# Net520.net
KiCad netlist of a schematic drawn in Altium Designer
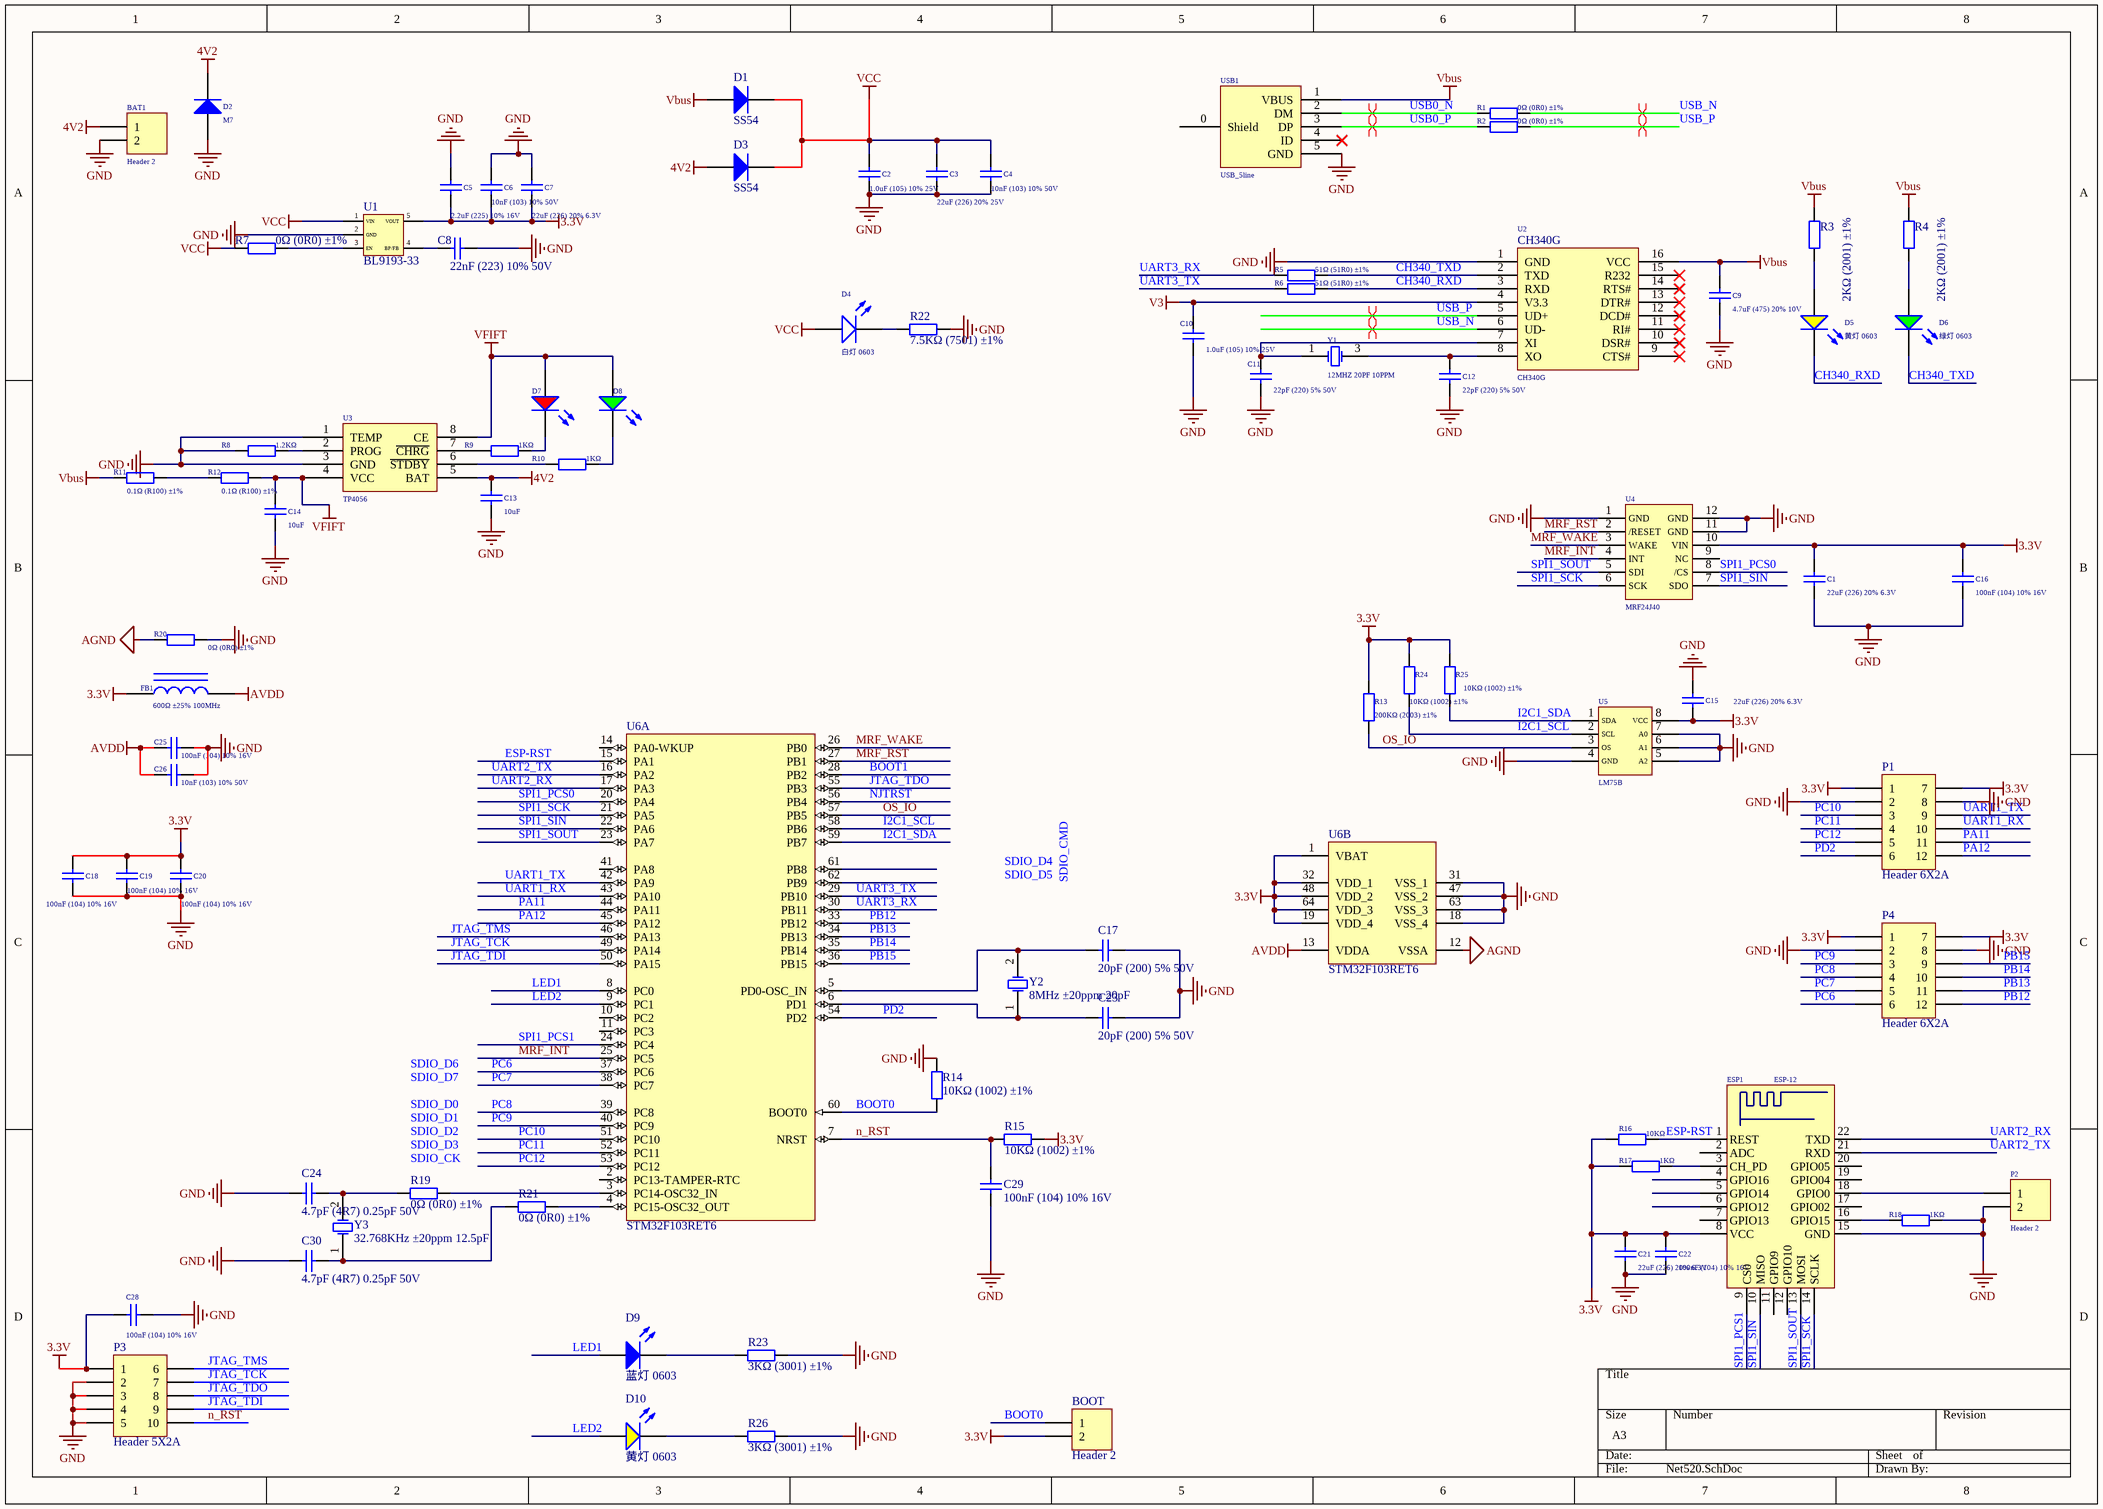
[diagram p0: Net520.SchDoc]

(export (version "E")
  (design (tool "Eeschema 10.0.6"))
  (components
    (comp (ref "BAT1")
      (value "Header 2")
      (footprint "HDR1X2")
      (description "Header, 2-Pin")
      (fields (field (name "PUBLISHER") "Altium Limited"))
      (libsource (lib "Sparks") (part "Header 2"))
    )
    (comp (ref "BOOT")
      (value "Header 2")
      (footprint "HDR1X2")
      (description "Header, 2-Pin")
      (fields (field (name "PUBLISHER") "Altium Limited"))
      (libsource (lib "Sparks") (part "Header 2"))
    )
    (comp (ref "C1")
      (value "22uF (226) 20% 6.3V")
      (footprint "0603_C")
      (description "贴片电容")
      (libsource (lib "Miscellaneous Devices LC") (part "0603 22uF (226) 20% 6.3V"))
    )
    (comp (ref "C2")
      (value "1.0uF (105) 10% 25V")
      (footprint "0402_C")
      (description "贴片电容")
      (libsource (lib "Miscellaneous Devices LC") (part "0402 1.0uF (105) 10% 25V"))
    )
    (comp (ref "C3")
      (value "22uF (226) 20% 25V")
      (footprint "0805_C")
      (description "贴片电容")
      (libsource (lib "Miscellaneous Devices LC") (part "0805 22uF (226) 20% 25V"))
    )
    (comp (ref "C4")
      (value "10nF (103) 10% 50V")
      (footprint "0402_C")
      (description "贴片电容")
      (libsource (lib "Miscellaneous Devices LC") (part "0402 10nF (103) 10% 50V"))
    )
    (comp (ref "C5")
      (value "2.2uF (225) 10% 16V")
      (footprint "0603_C")
      (description "贴片电容")
      (libsource (lib "Miscellaneous Devices LC") (part "0603 2.2uF (225) 10% 16V"))
    )
    (comp (ref "C6")
      (value "10nF (103) 10% 50V")
      (footprint "0402_C")
      (description "贴片电容")
      (libsource (lib "Miscellaneous Devices LC") (part "0402 10nF (103) 10% 50V"))
    )
    (comp (ref "C7")
      (value "22uF (226) 20% 6.3V")
      (footprint "0603_C")
      (description "贴片电容")
      (libsource (lib "Miscellaneous Devices LC") (part "0603 22uF (226) 20% 6.3V"))
    )
    (comp (ref "C8")
      (value "22nF (223) 10% 50V")
      (footprint "0402_C")
      (description "贴片电容")
      (libsource (lib "Miscellaneous Devices LC") (part "0402 22nF (223) 10% 50V"))
    )
    (comp (ref "C9")
      (value "4.7uF (475) 20% 10V")
      (footprint "0402_C")
      (description "贴片电容")
      (libsource (lib "Miscellaneous Devices LC") (part "0402 4.7uF (475) 20% 10V"))
    )
    (comp (ref "C10")
      (value "1.0uF (105) 10% 25V")
      (footprint "0402_C")
      (description "贴片电容")
      (libsource (lib "Miscellaneous Devices LC") (part "0402 1.0uF (105) 10% 25V"))
    )
    (comp (ref "C11")
      (value "22pF (220) 5% 50V")
      (footprint "0402_C")
      (description "贴片电容")
      (libsource (lib "Miscellaneous Devices LC") (part "0402 22pF (220) 5% 50V"))
    )
    (comp (ref "C12")
      (value "22pF (220) 5% 50V")
      (footprint "0402_C")
      (description "贴片电容")
      (libsource (lib "Miscellaneous Devices LC") (part "0402 22pF (220) 5% 50V"))
    )
    (comp (ref "C13")
      (value "10uF")
      (footprint "0402_C")
      (description "贴片电容")
      (libsource (lib "Cap") (part "0402 10uF (106) 20% 6.3V"))
    )
    (comp (ref "C14")
      (value "10uF")
      (footprint "0402_C")
      (description "贴片电容")
      (libsource (lib "Cap") (part "0402 10uF (106) 20% 6.3V"))
    )
    (comp (ref "C15")
      (value "22uF (226) 20% 6.3V")
      (footprint "0603_C")
      (description "贴片电容")
      (libsource (lib "Miscellaneous Devices LC") (part "0603 22uF (226) 20% 6.3V"))
    )
    (comp (ref "C16")
      (value "100nF (104) 10% 16V")
      (footprint "0402_C")
      (description "贴片电容")
      (libsource (lib "Miscellaneous Devices LC") (part "0402 100nF (104) 10% 16V"))
    )
    (comp (ref "C17")
      (value "20pF (200) 5% 50V")
      (footprint "0402_C")
      (description "贴片电容")
      (libsource (lib "Miscellaneous Devices LC") (part "0402 20pF (200) 5% 50V"))
    )
    (comp (ref "C18")
      (value "100nF (104) 10% 16V")
      (footprint "0402_C")
      (description "贴片电容")
      (libsource (lib "Miscellaneous Devices LC") (part "0402 100nF (104) 10% 16V"))
    )
    (comp (ref "C19")
      (value "100nF (104) 10% 16V")
      (footprint "0402_C")
      (description "贴片电容")
      (libsource (lib "Miscellaneous Devices LC") (part "0402 100nF (104) 10% 16V"))
    )
    (comp (ref "C20")
      (value "100nF (104) 10% 16V")
      (footprint "0402_C")
      (description "贴片电容")
      (libsource (lib "Miscellaneous Devices LC") (part "0402 100nF (104) 10% 16V"))
    )
    (comp (ref "C21")
      (value "22uF (226) 20% 6.3V")
      (footprint "0603_C")
      (description "贴片电容")
      (libsource (lib "Miscellaneous Devices LC") (part "0603 22uF (226) 20% 6.3V"))
    )
    (comp (ref "C22")
      (value "100nF (104) 10% 16V")
      (footprint "0402_C")
      (description "贴片电容")
      (libsource (lib "Miscellaneous Devices LC") (part "0402 100nF (104) 10% 16V"))
    )
    (comp (ref "C23")
      (value "20pF (200) 5% 50V")
      (footprint "0402_C")
      (description "贴片电容")
      (libsource (lib "Miscellaneous Devices LC") (part "0402 20pF (200) 5% 50V"))
    )
    (comp (ref "C24")
      (value "4.7pF (4R7) 0.25pF 50V")
      (footprint "0402_C")
      (description "贴片电容")
      (libsource (lib "Miscellaneous Devices LC") (part "0402 4.7pF (4R7) 0.25pF 50V"))
    )
    (comp (ref "C25")
      (value "100nF (104) 10% 16V")
      (footprint "0402_C")
      (description "贴片电容")
      (libsource (lib "Miscellaneous Devices LC") (part "0402 100nF (104) 10% 16V"))
    )
    (comp (ref "C26")
      (value "10nF (103) 10% 50V")
      (footprint "0402_C")
      (description "贴片电容")
      (libsource (lib "Miscellaneous Devices LC") (part "0402 10nF (103) 10% 50V"))
    )
    (comp (ref "C28")
      (value "100nF (104) 10% 16V")
      (footprint "0402_C")
      (description "贴片电容")
      (libsource (lib "Miscellaneous Devices LC") (part "0402 100nF (104) 10% 16V"))
    )
    (comp (ref "C29")
      (value "100nF (104) 10% 16V")
      (footprint "0402_C")
      (description "贴片电容")
      (libsource (lib "Miscellaneous Devices LC") (part "0402 100nF (104) 10% 16V"))
    )
    (comp (ref "C30")
      (value "4.7pF (4R7) 0.25pF 50V")
      (footprint "0402_C")
      (description "贴片电容")
      (libsource (lib "Miscellaneous Devices LC") (part "0402 4.7pF (4R7) 0.25pF 50V"))
    )
    (comp (ref "D1")
      (value "SS54")
      (footprint "SMA(DO-214AC)_S1")
      (description "二极管")
      (libsource (lib "Miscellaneous Devices LC") (part "SMA(DO-214AC) SS54"))
    )
    (comp (ref "D2")
      (value "M7")
      (footprint "SMA(DO-214AC)_S1")
      (description "二极管")
      (libsource (lib "Miscellaneous Devices LC") (part "SMA(DO-214AC) M7"))
    )
    (comp (ref "D3")
      (value "SS54")
      (footprint "SMA(DO-214AC)_S1")
      (description "二极管")
      (libsource (lib "Miscellaneous Devices LC") (part "SMA(DO-214AC) SS54"))
    )
    (comp (ref "D4")
      (value "白灯 0603")
      (footprint "0603_LED_S1")
      (description "发光二极管")
      (libsource (lib "Miscellaneous Devices LC") (part "0603 白灯"))
    )
    (comp (ref "D5")
      (value "黄灯 0603")
      (footprint "0603_LED_S1")
      (description "发光二极管")
      (libsource (lib "Miscellaneous Devices LC") (part "0603 黄灯"))
    )
    (comp (ref "D6")
      (value "绿灯 0603")
      (footprint "0603_LED_S1")
      (description "发光二极管")
      (libsource (lib "Miscellaneous Devices LC") (part "0603 绿灯"))
    )
    (comp (ref "D7")
      (value "红灯 0603")
      (footprint "0603_LED_S1")
      (description "发光二极管")
      (libsource (lib "LED") (part "0603 红灯"))
    )
    (comp (ref "D8")
      (value "绿灯 0603")
      (footprint "0603_LED_S1")
      (description "发光二极管")
      (libsource (lib "LED") (part "0603 绿灯"))
    )
    (comp (ref "D9")
      (value "蓝灯 0603")
      (footprint "0603_LED_S1")
      (description "发光二极管")
      (libsource (lib "Miscellaneous Devices LC") (part "0603 蓝灯"))
    )
    (comp (ref "D10")
      (value "黄灯 0603")
      (footprint "0603_LED_S1")
      (description "发光二极管")
      (libsource (lib "Miscellaneous Devices LC") (part "0603 黄灯"))
    )
    (comp (ref "ESP1") (value "ESP-12") (footprint "ESP-12") (libsource (lib "2号库") (part "ESP-12")))
    (comp (ref "FB1")
      (value "600Ω ±25% 100MHz")
      (footprint "0805_L")
      (description "贴片磁珠")
      (libsource (lib "Miscellaneous Devices LC") (part "0805 600Ω 25% 100MHz"))
    )
    (comp (ref "P1")
      (value "Header 6X2A")
      (footprint "SMT-HEADER 6*2")
      (description "Header, 6-Pin, Dual row")
      (fields (field (name "PUBLISHER") "Altium Limited"))
      (libsource (lib "Miscellaneous Connectors") (part "Header 6X2A"))
    )
    (comp (ref "P2")
      (value "Header 2")
      (footprint "HDR1X2")
      (description "Header, 2-Pin")
      (fields (field (name "PUBLISHER") "Altium Limited"))
      (libsource (lib "Sparks") (part "Header 2"))
    )
    (comp (ref "P3")
      (value "Header 5X2A")
      (footprint "SMT HEADER 5*2")
      (description "Header, 5-Pin, Dual row")
      (fields (field (name "PUBLISHER") "Altium Limited"))
      (libsource (lib "Miscellaneous Connectors") (part "Header 5X2A"))
    )
    (comp (ref "P4")
      (value "Header 6X2A")
      (footprint "SMT-HEADER 6*2")
      (description "Header, 6-Pin, Dual row")
      (fields (field (name "PUBLISHER") "Altium Limited"))
      (libsource (lib "Miscellaneous Connectors") (part "Header 6X2A"))
    )
    (comp (ref "R1")
      (value "0Ω (0R0) ±1%")
      (footprint "0402_R")
      (description "贴片电阻")
      (libsource (lib "Miscellaneous Devices LC") (part "0402 0Ω (0R0) 1%"))
    )
    (comp (ref "R2")
      (value "0Ω (0R0) ±1%")
      (footprint "0402_R")
      (description "贴片电阻")
      (libsource (lib "Miscellaneous Devices LC") (part "0402 0Ω (0R0) 1%"))
    )
    (comp (ref "R3")
      (value "2KΩ (2001) ±1%")
      (footprint "0402_R")
      (description "贴片电阻")
      (libsource (lib "Miscellaneous Devices LC") (part "0402 2KΩ (2001) 1%"))
    )
    (comp (ref "R4")
      (value "2KΩ (2001) ±1%")
      (footprint "0402_R")
      (description "贴片电阻")
      (libsource (lib "") (part "0402 2KΩ (2001) 1%_1"))
    )
    (comp (ref "R5")
      (value "51Ω (51R0) ±1%")
      (footprint "0402_R")
      (description "贴片电阻")
      (libsource (lib "Miscellaneous Devices LC") (part "0402 51Ω (51R0) 1%"))
    )
    (comp (ref "R6")
      (value "51Ω (51R0) ±1%")
      (footprint "0402_R")
      (description "贴片电阻")
      (libsource (lib "Miscellaneous Devices LC") (part "0402 51Ω (51R0) 1%"))
    )
    (comp (ref "R7")
      (value "0Ω (0R0) ±1%")
      (footprint "0402_R")
      (description "贴片电阻")
      (libsource (lib "Miscellaneous Devices LC") (part "0402 0Ω (0R0) 1%"))
    )
    (comp (ref "R8")
      (value "1.2KΩ")
      (footprint "0402_R")
      (description "贴片电阻")
      (libsource (lib "RES") (part "0402 1.2KΩ (1201) 1%"))
    )
    (comp (ref "R9")
      (value "1KΩ")
      (footprint "0402_R")
      (description "贴片电阻")
      (libsource (lib "RES") (part "0402 1KΩ (1001) 1%"))
    )
    (comp (ref "R10")
      (value "1KΩ")
      (footprint "0402_R")
      (description "贴片电阻")
      (libsource (lib "RES") (part "0402 1KΩ (1001) 1%"))
    )
    (comp (ref "R11")
      (value "0.1Ω (R100) ±1%")
      (footprint "1206_R")
      (description "贴片电阻")
      (libsource (lib "Miscellaneous Devices LC") (part "1206 0.1Ω (R100) 1%"))
    )
    (comp (ref "R12")
      (value "0.1Ω (R100) ±1%")
      (footprint "1206_R")
      (description "贴片电阻")
      (libsource (lib "Miscellaneous Devices LC") (part "1206 0.1Ω (R100) 1%"))
    )
    (comp (ref "R13")
      (value "200KΩ (2003) ±1%")
      (footprint "0402_R")
      (description "贴片电阻")
      (libsource (lib "Miscellaneous Devices LC") (part "0402 200KΩ (2003) 1%"))
    )
    (comp (ref "R14")
      (value "10KΩ (1002) ±1%")
      (footprint "0402_R")
      (description "贴片电阻")
      (libsource (lib "Miscellaneous Devices LC") (part "0402 10KΩ (1002) 1%"))
    )
    (comp (ref "R15")
      (value "10KΩ (1002) ±1%")
      (footprint "0402_R")
      (description "贴片电阻")
      (libsource (lib "") (part "0402 10KΩ (1002) 1%_1"))
    )
    (comp (ref "R16")
      (value "10KΩ")
      (footprint "0603_R")
      (description "贴片电阻")
      (libsource (lib "RES") (part "0603 10KΩ (1002) 1%"))
    )
    (comp (ref "R17")
      (value "1KΩ")
      (footprint "0603_R")
      (description "贴片电阻")
      (libsource (lib "RES") (part "0603 1KΩ (1001) 1%"))
    )
    (comp (ref "R18")
      (value "1KΩ")
      (footprint "0603_R")
      (description "贴片电阻")
      (libsource (lib "RES") (part "0603 1KΩ (1001) 1%"))
    )
    (comp (ref "R19")
      (value "0Ω (0R0) ±1%")
      (footprint "0402_R")
      (description "贴片电阻")
      (libsource (lib "Miscellaneous Devices LC") (part "0402 0Ω (0R0) 1%"))
    )
    (comp (ref "R20")
      (value "0Ω (0R0) ±1%")
      (footprint "0402_R")
      (description "贴片电阻")
      (libsource (lib "Miscellaneous Devices LC") (part "0402 0Ω (0R0) 1%"))
    )
    (comp (ref "R21")
      (value "0Ω (0R0) ±1%")
      (footprint "0402_R")
      (description "贴片电阻")
      (libsource (lib "Miscellaneous Devices LC") (part "0402 0Ω (0R0) 1%"))
    )
    (comp (ref "R22")
      (value "7.5KΩ (7501) ±1%")
      (footprint "0402_R")
      (description "贴片电阻")
      (libsource (lib "Miscellaneous Devices LC") (part "0402 7.5KΩ (7501) 1%"))
    )
    (comp (ref "R23")
      (value "3KΩ (3001) ±1%")
      (footprint "0603_R")
      (description "贴片电阻")
      (libsource (lib "Miscellaneous Devices LC") (part "0603 3KΩ (3001) 1%"))
    )
    (comp (ref "R24")
      (value "10KΩ (1002) ±1%")
      (footprint "0402_R")
      (description "贴片电阻")
      (libsource (lib "Miscellaneous Devices LC") (part "0402 10KΩ (1002) 1%"))
    )
    (comp (ref "R25")
      (value "10KΩ (1002) ±1%")
      (footprint "0402_R")
      (description "贴片电阻")
      (libsource (lib "Miscellaneous Devices LC") (part "0402 10KΩ (1002) 1%"))
    )
    (comp (ref "R26")
      (value "3KΩ (3001) ±1%")
      (footprint "0603_R")
      (description "贴片电阻")
      (libsource (lib "Miscellaneous Devices LC") (part "0603 3KΩ (3001) 1%"))
    )
    (comp (ref "U1")
      (value "BL9193-33")
      (footprint "LC-SOT-23-5")
      (libsource (lib "jlcUser") (part "BL9193-33"))
    )
    (comp (ref "U2")
      (value "CH340G")
      (footprint "SOIC-16_150mil")
      (description "USB")
      (libsource (lib "Miscellaneous Devices LC") (part "CH340G_[C14267]"))
    )
    (comp (ref "U3")
      (value "TP4056")
      (footprint "SOP-8_EP_150mil")
      (description "电池电源管理")
      (libsource (lib "IC") (part "TP4056_[C16581]"))
    )
    (comp (ref "U4") (value "MRF24J40") (footprint "MRF24J40") (libsource (lib "2号库") (part "MRF24J40")))
    (comp (ref "U5")
      (value "LM75B")
      (footprint "LC-SOIC-8_150mil")
      (libsource (lib "jlcUser") (part "LM75B"))
    )
    (comp (ref "U6")
      (value "STM32F103RET6")
      (footprint "LQFP-64_10x10x05P")
      (description "ARM")
      (libsource (lib "Miscellaneous Devices LC") (part "STM32F103RET6"))
    )
    (comp (ref "USB1")
      (value "USB_5line")
      (footprint "USB-MICRO-5P-2F")
      (libsource (lib "2号库") (part "USB_5line"))
    )
    (comp (ref "Y1")
      (value "12MHZ 20PF 10PPM")
      (footprint "SMD-3225_4P")
      (description "贴片晶振")
      (libsource (lib "Miscellaneous Devices LC") (part "SMD-3225_4P  12MHZ 20PF 10PPM"))
    )
    (comp (ref "Y2")
      (value "8MHz ±20ppm 20pF")
      (footprint "SMD-5032_2P")
      (description "贴片晶振")
      (libsource (lib "Miscellaneous Devices LC") (part "SMD-5032_2P 8MHz 20ppm 20pF"))
    )
    (comp (ref "Y3")
      (value "32.768KHz ±20ppm 12.5pF")
      (footprint "SMD-3215_2P FC - 135")
      (description "贴片晶振")
      (libsource (lib "Miscellaneous Devices LC") (part "SMD-3215_2P 32.768KHz 20ppm 12.5pF"))
    )
  )
  (nets
    (net (code "1") (name "/BOOT0") (class "Default")
      (node (ref "BOOT") (pin "1") (pinfunction "1_1") (pintype "passive"))
      (node (ref "R14") (pin "1") (pinfunction "1_1") (pintype "passive"))
      (node (ref "U6") (pin "60") (pinfunction "BOOT0_60") (pintype "input"))
    )
    (net (code "2") (name "/BOOT1") (class "Default")
      (node (ref "U6") (pin "28") (pinfunction "PB2_28") (pintype "bidirectional"))
    )
    (net (code "3") (name "/CH340_RXD") (class "Default")
      (node (ref "D5") (pin "K") (pinfunction "K_K") (pintype "passive"))
      (node (ref "R6") (pin "2") (pinfunction "2_2") (pintype "passive"))
      (node (ref "U2") (pin "3") (pinfunction "RXD_3") (pintype "passive"))
    )
    (net (code "4") (name "/CH340_TXD") (class "Default")
      (node (ref "D6") (pin "K") (pinfunction "K_K") (pintype "passive"))
      (node (ref "R5") (pin "2") (pinfunction "2_2") (pintype "passive"))
      (node (ref "U2") (pin "2") (pinfunction "TXD_2") (pintype "passive"))
    )
    (net (code "5") (name "/ESP-RST") (class "Default")
      (node (ref "ESP1") (pin "1") (pinfunction "REST_1") (pintype "passive"))
      (node (ref "R16") (pin "2") (pinfunction "2_2") (pintype "passive"))
      (node (ref "U6") (pin "15") (pinfunction "PA1_15") (pintype "bidirectional"))
    )
    (net (code "6") (name "/I2C1_SCL") (class "Default")
      (node (ref "R24") (pin "1") (pinfunction "1_1") (pintype "passive"))
      (node (ref "U5") (pin "2") (pinfunction "SCL_2") (pintype "passive"))
      (node (ref "U6") (pin "58") (pinfunction "PB6_58") (pintype "bidirectional"))
    )
    (net (code "7") (name "/I2C1_SDA") (class "Default")
      (node (ref "R25") (pin "1") (pinfunction "1_1") (pintype "passive"))
      (node (ref "U5") (pin "1") (pinfunction "SDA_1") (pintype "passive"))
      (node (ref "U6") (pin "59") (pinfunction "PB7_59") (pintype "bidirectional"))
    )
    (net (code "8") (name "/JTAG_TCK") (class "Default")
      (node (ref "P3") (pin "7") (pinfunction "7_7") (pintype "passive"))
      (node (ref "U6") (pin "49") (pinfunction "PA14_49") (pintype "bidirectional"))
    )
    (net (code "9") (name "/JTAG_TDI") (class "Default")
      (node (ref "P3") (pin "9") (pinfunction "9_9") (pintype "passive"))
      (node (ref "U6") (pin "50") (pinfunction "PA15_50") (pintype "bidirectional"))
    )
    (net (code "10") (name "/JTAG_TDO") (class "Default")
      (node (ref "P3") (pin "8") (pinfunction "8_8") (pintype "passive"))
      (node (ref "U6") (pin "55") (pinfunction "PB3_55") (pintype "bidirectional"))
    )
    (net (code "11") (name "/JTAG_TMS") (class "Default")
      (node (ref "P3") (pin "6") (pinfunction "6_6") (pintype "passive"))
      (node (ref "U6") (pin "46") (pinfunction "PA13_46") (pintype "bidirectional"))
    )
    (net (code "12") (name "/LED1") (class "Default")
      (node (ref "D9") (pin "A") (pinfunction "A_A") (pintype "passive"))
      (node (ref "U6") (pin "8") (pinfunction "PC0_8") (pintype "bidirectional"))
    )
    (net (code "13") (name "/LED2") (class "Default")
      (node (ref "D10") (pin "A") (pinfunction "A_A") (pintype "passive"))
      (node (ref "U6") (pin "9") (pinfunction "PC1_9") (pintype "bidirectional"))
    )
    (net (code "14") (name "/MRF_INT") (class "Default")
      (node (ref "U4") (pin "4") (pinfunction "INT_4") (pintype "passive"))
      (node (ref "U6") (pin "25") (pinfunction "PC5_25") (pintype "bidirectional"))
    )
    (net (code "15") (name "/MRF_RST") (class "Default")
      (node (ref "U4") (pin "2") (pinfunction "/RESET_2") (pintype "passive"))
      (node (ref "U6") (pin "27") (pinfunction "PB1_27") (pintype "bidirectional"))
    )
    (net (code "16") (name "/MRF_WAKE") (class "Default")
      (node (ref "U4") (pin "3") (pinfunction "WAKE_3") (pintype "passive"))
      (node (ref "U6") (pin "26") (pinfunction "PB0_26") (pintype "bidirectional"))
    )
    (net (code "17") (name "/NJTRST") (class "Default")
      (node (ref "U6") (pin "56") (pinfunction "PB4_56") (pintype "bidirectional"))
    )
    (net (code "18") (name "/OS_IO") (class "Default")
      (node (ref "R13") (pin "1") (pinfunction "1_1") (pintype "passive"))
      (node (ref "U5") (pin "3") (pinfunction "OS_3") (pintype "passive"))
      (node (ref "U6") (pin "57") (pinfunction "PB5_57") (pintype "bidirectional"))
    )
    (net (code "19") (name "/PA11") (class "Default")
      (node (ref "P1") (pin "11") (pinfunction "11_11") (pintype "passive"))
      (node (ref "U6") (pin "44") (pinfunction "PA11_44") (pintype "bidirectional"))
    )
    (net (code "20") (name "/PA12") (class "Default")
      (node (ref "P1") (pin "12") (pinfunction "12_12") (pintype "passive"))
      (node (ref "U6") (pin "45") (pinfunction "PA12_45") (pintype "bidirectional"))
    )
    (net (code "21") (name "/PB12") (class "Default")
      (node (ref "P4") (pin "12") (pinfunction "12_12") (pintype "passive"))
      (node (ref "U6") (pin "33") (pinfunction "PB12_33") (pintype "bidirectional"))
    )
    (net (code "22") (name "/PB13") (class "Default")
      (node (ref "P4") (pin "11") (pinfunction "11_11") (pintype "passive"))
      (node (ref "U6") (pin "34") (pinfunction "PB13_34") (pintype "bidirectional"))
    )
    (net (code "23") (name "/PB14") (class "Default")
      (node (ref "P4") (pin "10") (pinfunction "10_10") (pintype "passive"))
      (node (ref "U6") (pin "35") (pinfunction "PB14_35") (pintype "bidirectional"))
    )
    (net (code "24") (name "/PB15") (class "Default")
      (node (ref "P4") (pin "9") (pinfunction "9_9") (pintype "passive"))
      (node (ref "U6") (pin "36") (pinfunction "PB15_36") (pintype "bidirectional"))
    )
    (net (code "25") (name "/PC6") (class "Default")
      (node (ref "P4") (pin "6") (pinfunction "6_6") (pintype "passive"))
      (node (ref "U6") (pin "37") (pinfunction "PC6_37") (pintype "bidirectional"))
    )
    (net (code "26") (name "/PC7") (class "Default")
      (node (ref "P4") (pin "5") (pinfunction "5_5") (pintype "passive"))
      (node (ref "U6") (pin "38") (pinfunction "PC7_38") (pintype "bidirectional"))
    )
    (net (code "27") (name "/PC8") (class "Default")
      (node (ref "P4") (pin "4") (pinfunction "4_4") (pintype "passive"))
      (node (ref "U6") (pin "39") (pinfunction "PC8_39") (pintype "bidirectional"))
    )
    (net (code "28") (name "/PC9") (class "Default")
      (node (ref "P4") (pin "3") (pinfunction "3_3") (pintype "passive"))
      (node (ref "U6") (pin "40") (pinfunction "PC9_40") (pintype "bidirectional"))
    )
    (net (code "29") (name "/PC10") (class "Default")
      (node (ref "P1") (pin "3") (pinfunction "3_3") (pintype "passive"))
      (node (ref "U6") (pin "51") (pinfunction "PC10_51") (pintype "bidirectional"))
    )
    (net (code "30") (name "/PC11") (class "Default")
      (node (ref "P1") (pin "4") (pinfunction "4_4") (pintype "passive"))
      (node (ref "U6") (pin "52") (pinfunction "PC11_52") (pintype "bidirectional"))
    )
    (net (code "31") (name "/PC12") (class "Default")
      (node (ref "P1") (pin "5") (pinfunction "5_5") (pintype "passive"))
      (node (ref "U6") (pin "53") (pinfunction "PC12_53") (pintype "bidirectional"))
    )
    (net (code "32") (name "/PD2") (class "Default")
      (node (ref "P1") (pin "6") (pinfunction "6_6") (pintype "passive"))
      (node (ref "U6") (pin "54") (pinfunction "PD2_54") (pintype "bidirectional"))
    )
    (net (code "43") (name "/SPI1_PCS0") (class "Default")
      (node (ref "U4") (pin "8") (pinfunction "/CS_8") (pintype "passive"))
      (node (ref "U6") (pin "20") (pinfunction "PA4_20") (pintype "bidirectional"))
    )
    (net (code "44") (name "/SPI1_PCS1") (class "Default")
      (node (ref "ESP1") (pin "9") (pinfunction "CS0_9") (pintype "passive"))
      (node (ref "U6") (pin "24") (pinfunction "PC4_24") (pintype "bidirectional"))
    )
    (net (code "45") (name "/SPI1_SCK") (class "Default")
      (node (ref "ESP1") (pin "14") (pinfunction "SCLK_14") (pintype "passive"))
      (node (ref "U4") (pin "6") (pinfunction "SCK_6") (pintype "passive"))
      (node (ref "U6") (pin "21") (pinfunction "PA5_21") (pintype "bidirectional"))
    )
    (net (code "46") (name "/SPI1_SIN") (class "Default")
      (node (ref "ESP1") (pin "10") (pinfunction "MISO_10") (pintype "passive"))
      (node (ref "U4") (pin "7") (pinfunction "SDO_7") (pintype "passive"))
      (node (ref "U6") (pin "22") (pinfunction "PA6_22") (pintype "bidirectional"))
    )
    (net (code "47") (name "/SPI1_SOUT") (class "Default")
      (node (ref "ESP1") (pin "13") (pinfunction "MOSI_13") (pintype "passive"))
      (node (ref "U4") (pin "5") (pinfunction "SDI_5") (pintype "passive"))
      (node (ref "U6") (pin "23") (pinfunction "PA7_23") (pintype "bidirectional"))
    )
    (net (code "48") (name "/UART1_RX") (class "Default")
      (node (ref "P1") (pin "10") (pinfunction "10_10") (pintype "passive"))
      (node (ref "U6") (pin "43") (pinfunction "PA10_43") (pintype "bidirectional"))
    )
    (net (code "49") (name "/UART1_TX") (class "Default")
      (node (ref "P1") (pin "9") (pinfunction "9_9") (pintype "passive"))
      (node (ref "U6") (pin "42") (pinfunction "PA9_42") (pintype "bidirectional"))
    )
    (net (code "50") (name "/UART2_RX") (class "Default")
      (node (ref "ESP1") (pin "22") (pinfunction "TXD_22") (pintype "passive"))
      (node (ref "U6") (pin "17") (pinfunction "PA3_17") (pintype "bidirectional"))
    )
    (net (code "51") (name "/UART2_TX") (class "Default")
      (node (ref "ESP1") (pin "21") (pinfunction "RXD_21") (pintype "passive"))
      (node (ref "U6") (pin "16") (pinfunction "PA2_16") (pintype "bidirectional"))
    )
    (net (code "52") (name "/UART3_RX") (class "Default")
      (node (ref "R5") (pin "1") (pinfunction "1_1") (pintype "passive"))
      (node (ref "U6") (pin "30") (pinfunction "PB11_30") (pintype "bidirectional"))
    )
    (net (code "53") (name "/UART3_TX") (class "Default")
      (node (ref "R6") (pin "1") (pinfunction "1_1") (pintype "passive"))
      (node (ref "U6") (pin "29") (pinfunction "PB10_29") (pintype "bidirectional"))
    )
    (net (code "54") (name "/USB0_N") (class "Default")
      (node (ref "R1") (pin "1") (pinfunction "1_1") (pintype "passive"))
      (node (ref "USB1") (pin "2") (pinfunction "DM_2") (pintype "passive"))
    )
    (net (code "55") (name "/USB0_P") (class "Default")
      (node (ref "R2") (pin "1") (pinfunction "1_1") (pintype "passive"))
      (node (ref "USB1") (pin "3") (pinfunction "DP_3") (pintype "passive"))
    )
    (net (code "56") (name "/USB_N") (class "Default")
      (node (ref "R1") (pin "2") (pinfunction "2_2") (pintype "passive"))
      (node (ref "U2") (pin "6") (pinfunction "UD-_6") (pintype "passive"))
    )
    (net (code "57") (name "/USB_P") (class "Default")
      (node (ref "R2") (pin "2") (pinfunction "2_2") (pintype "passive"))
      (node (ref "U2") (pin "5") (pinfunction "UD+_5") (pintype "passive"))
    )
    (net (code "58") (name "/n_RST") (class "Default")
      (node (ref "C29") (pin "2") (pinfunction "2_2") (pintype "passive"))
      (node (ref "P3") (pin "10") (pinfunction "10_10") (pintype "passive"))
      (node (ref "R15") (pin "2") (pinfunction "2_2") (pintype "passive"))
      (node (ref "U6") (pin "7") (pinfunction "NRST_7") (pintype "bidirectional"))
    )
    (net (code "59") (name "3.3V") (class "Default")
      (node (ref "BOOT") (pin "2") (pinfunction "2_2") (pintype "passive"))
      (node (ref "C1") (pin "2") (pinfunction "2_2") (pintype "passive"))
      (node (ref "C15") (pin "1") (pinfunction "1_1") (pintype "passive"))
      (node (ref "C16") (pin "2") (pinfunction "2_2") (pintype "passive"))
      (node (ref "C18") (pin "2") (pinfunction "2_2") (pintype "passive"))
      (node (ref "C19") (pin "2") (pinfunction "2_2") (pintype "passive"))
      (node (ref "C20") (pin "2") (pinfunction "2_2") (pintype "passive"))
      (node (ref "C21") (pin "2") (pinfunction "2_2") (pintype "passive"))
      (node (ref "C22") (pin "2") (pinfunction "2_2") (pintype "passive"))
      (node (ref "C28") (pin "1") (pinfunction "1_1") (pintype "passive"))
      (node (ref "C5") (pin "1") (pinfunction "1_1") (pintype "passive"))
      (node (ref "C6") (pin "1") (pinfunction "1_1") (pintype "passive"))
      (node (ref "C7") (pin "1") (pinfunction "1_1") (pintype "passive"))
      (node (ref "ESP1") (pin "8") (pinfunction "VCC_8") (pintype "passive"))
      (node (ref "FB1") (pin "1") (pinfunction "1_1") (pintype "passive"))
      (node (ref "P1") (pin "1") (pinfunction "1_1") (pintype "passive"))
      (node (ref "P1") (pin "7") (pinfunction "7_7") (pintype "passive"))
      (node (ref "P3") (pin "1") (pinfunction "1_1") (pintype "passive"))
      (node (ref "P4") (pin "1") (pinfunction "1_1") (pintype "passive"))
      (node (ref "P4") (pin "7") (pinfunction "7_7") (pintype "passive"))
      (node (ref "R13") (pin "2") (pinfunction "2_2") (pintype "passive"))
      (node (ref "R15") (pin "1") (pinfunction "1_1") (pintype "passive"))
      (node (ref "R16") (pin "1") (pinfunction "1_1") (pintype "passive"))
      (node (ref "R17") (pin "1") (pinfunction "1_1") (pintype "passive"))
      (node (ref "R24") (pin "2") (pinfunction "2_2") (pintype "passive"))
      (node (ref "R25") (pin "2") (pinfunction "2_2") (pintype "passive"))
      (node (ref "U1") (pin "5") (pinfunction "VOUT_5") (pintype "passive"))
      (node (ref "U4") (pin "10") (pinfunction "VIN_10") (pintype "passive"))
      (node (ref "U5") (pin "8") (pinfunction "VCC_8") (pintype "passive"))
      (node (ref "U6") (pin "1") (pinfunction "VBAT_1") (pintype "power_in"))
      (node (ref "U6") (pin "19") (pinfunction "VDD_4_19") (pintype "power_in"))
      (node (ref "U6") (pin "32") (pinfunction "VDD_1_32") (pintype "power_in"))
      (node (ref "U6") (pin "48") (pinfunction "VDD_2_48") (pintype "power_in"))
      (node (ref "U6") (pin "64") (pinfunction "VDD_3_64") (pintype "power_in"))
    )
    (net (code "60") (name "4V2") (class "Default")
      (node (ref "BAT1") (pin "1") (pinfunction "1_1") (pintype "passive"))
      (node (ref "C13") (pin "2") (pinfunction "2_2") (pintype "passive"))
      (node (ref "D2") (pin "2") (pinfunction "K_2") (pintype "passive"))
      (node (ref "D3") (pin "1") (pinfunction "A_1") (pintype "passive"))
      (node (ref "U3") (pin "5") (pinfunction "BAT_5") (pintype "passive"))
    )
    (net (code "61") (name "AGND") (class "Default")
      (node (ref "R20") (pin "1") (pinfunction "1_1") (pintype "passive"))
      (node (ref "U6") (pin "12") (pinfunction "VSSA_12") (pintype "power_in"))
    )
    (net (code "62") (name "AVDD") (class "Default")
      (node (ref "C25") (pin "1") (pinfunction "1_1") (pintype "passive"))
      (node (ref "C26") (pin "1") (pinfunction "1_1") (pintype "passive"))
      (node (ref "FB1") (pin "2") (pinfunction "2_2") (pintype "passive"))
      (node (ref "U6") (pin "13") (pinfunction "VDDA_13") (pintype "power_in"))
    )
    (net (code "63") (name "GND") (class "Default")
      (node (ref "BAT1") (pin "2") (pinfunction "2_2") (pintype "passive"))
      (node (ref "C1") (pin "1") (pinfunction "1_1") (pintype "passive"))
      (node (ref "C10") (pin "1") (pinfunction "1_1") (pintype "passive"))
      (node (ref "C11") (pin "1") (pinfunction "1_1") (pintype "passive"))
      (node (ref "C12") (pin "1") (pinfunction "1_1") (pintype "passive"))
      (node (ref "C13") (pin "1") (pinfunction "1_1") (pintype "passive"))
      (node (ref "C14") (pin "1") (pinfunction "1_1") (pintype "passive"))
      (node (ref "C15") (pin "2") (pinfunction "2_2") (pintype "passive"))
      (node (ref "C16") (pin "1") (pinfunction "1_1") (pintype "passive"))
      (node (ref "C17") (pin "1") (pinfunction "1_1") (pintype "passive"))
      (node (ref "C18") (pin "1") (pinfunction "1_1") (pintype "passive"))
      (node (ref "C19") (pin "1") (pinfunction "1_1") (pintype "passive"))
      (node (ref "C2") (pin "1") (pinfunction "1_1") (pintype "passive"))
      (node (ref "C20") (pin "1") (pinfunction "1_1") (pintype "passive"))
      (node (ref "C21") (pin "1") (pinfunction "1_1") (pintype "passive"))
      (node (ref "C22") (pin "1") (pinfunction "1_1") (pintype "passive"))
      (node (ref "C23") (pin "1") (pinfunction "1_1") (pintype "passive"))
      (node (ref "C24") (pin "1") (pinfunction "1_1") (pintype "passive"))
      (node (ref "C25") (pin "2") (pinfunction "2_2") (pintype "passive"))
      (node (ref "C26") (pin "2") (pinfunction "2_2") (pintype "passive"))
      (node (ref "C28") (pin "2") (pinfunction "2_2") (pintype "passive"))
      (node (ref "C29") (pin "1") (pinfunction "1_1") (pintype "passive"))
      (node (ref "C3") (pin "1") (pinfunction "1_1") (pintype "passive"))
      (node (ref "C30") (pin "1") (pinfunction "1_1") (pintype "passive"))
      (node (ref "C4") (pin "1") (pinfunction "1_1") (pintype "passive"))
      (node (ref "C5") (pin "2") (pinfunction "2_2") (pintype "passive"))
      (node (ref "C6") (pin "2") (pinfunction "2_2") (pintype "passive"))
      (node (ref "C7") (pin "2") (pinfunction "2_2") (pintype "passive"))
      (node (ref "C8") (pin "2") (pinfunction "2_2") (pintype "passive"))
      (node (ref "C9") (pin "1") (pinfunction "1_1") (pintype "passive"))
      (node (ref "D2") (pin "1") (pinfunction "A_1") (pintype "passive"))
      (node (ref "ESP1") (pin "15") (pinfunction "GND_15") (pintype "passive"))
      (node (ref "P1") (pin "2") (pinfunction "2_2") (pintype "passive"))
      (node (ref "P1") (pin "8") (pinfunction "8_8") (pintype "passive"))
      (node (ref "P2") (pin "2") (pinfunction "2_2") (pintype "passive"))
      (node (ref "P3") (pin "2") (pinfunction "2_2") (pintype "passive"))
      (node (ref "P3") (pin "3") (pinfunction "3_3") (pintype "passive"))
      (node (ref "P3") (pin "4") (pinfunction "4_4") (pintype "passive"))
      (node (ref "P3") (pin "5") (pinfunction "5_5") (pintype "passive"))
      (node (ref "P4") (pin "2") (pinfunction "2_2") (pintype "passive"))
      (node (ref "P4") (pin "8") (pinfunction "8_8") (pintype "passive"))
      (node (ref "R14") (pin "2") (pinfunction "2_2") (pintype "passive"))
      (node (ref "R18") (pin "2") (pinfunction "2_2") (pintype "passive"))
      (node (ref "R20") (pin "2") (pinfunction "2_2") (pintype "passive"))
      (node (ref "R22") (pin "2") (pinfunction "2_2") (pintype "passive"))
      (node (ref "R23") (pin "2") (pinfunction "2_2") (pintype "passive"))
      (node (ref "R26") (pin "2") (pinfunction "2_2") (pintype "passive"))
      (node (ref "R8") (pin "1") (pinfunction "1_1") (pintype "passive"))
      (node (ref "U1") (pin "2") (pinfunction "GND_2") (pintype "passive"))
      (node (ref "U2") (pin "1") (pinfunction "GND_1") (pintype "passive"))
      (node (ref "U3") (pin "1") (pinfunction "TEMP_1") (pintype "passive"))
      (node (ref "U3") (pin "3") (pinfunction "GND_3") (pintype "passive"))
      (node (ref "U4") (pin "1") (pinfunction "GND_1") (pintype "passive"))
      (node (ref "U4") (pin "11") (pinfunction "GND_11") (pintype "passive"))
      (node (ref "U4") (pin "12") (pinfunction "GND_12") (pintype "passive"))
      (node (ref "U5") (pin "4") (pinfunction "GND_4") (pintype "passive"))
      (node (ref "U5") (pin "5") (pinfunction "A2_5") (pintype "passive"))
      (node (ref "U5") (pin "6") (pinfunction "A1_6") (pintype "passive"))
      (node (ref "U5") (pin "7") (pinfunction "A0_7") (pintype "passive"))
      (node (ref "U6") (pin "18") (pinfunction "VSS_4_18") (pintype "power_in"))
      (node (ref "U6") (pin "31") (pinfunction "VSS_1_31") (pintype "power_in"))
      (node (ref "U6") (pin "47") (pinfunction "VSS_2_47") (pintype "power_in"))
      (node (ref "U6") (pin "63") (pinfunction "VSS_3_63") (pintype "power_in"))
      (node (ref "USB1") (pin "5") (pinfunction "GND_5") (pintype "passive"))
    )
    (net (code "64") (name "Net-(D4-PadK)") (class "Default")
      (node (ref "D4") (pin "K") (pinfunction "K_K") (pintype "passive"))
      (node (ref "R22") (pin "1") (pinfunction "1_1") (pintype "passive"))
    )
    (net (code "65") (name "Net-(D5-PadA)") (class "Default")
      (node (ref "D5") (pin "A") (pinfunction "A_A") (pintype "passive"))
      (node (ref "R3") (pin "1") (pinfunction "1_1") (pintype "passive"))
    )
    (net (code "66") (name "Net-(D6-PadA)") (class "Default")
      (node (ref "D6") (pin "A") (pinfunction "A_A") (pintype "passive"))
      (node (ref "R4") (pin "2") (pinfunction "2_2") (pintype "passive"))
    )
    (net (code "67") (name "Net-(D7-PadK)") (class "Default")
      (node (ref "D7") (pin "K") (pinfunction "K_K") (pintype "passive"))
      (node (ref "R9") (pin "2") (pinfunction "2_2") (pintype "passive"))
    )
    (net (code "68") (name "Net-(D8-PadK)") (class "Default")
      (node (ref "D8") (pin "K") (pinfunction "K_K") (pintype "passive"))
      (node (ref "R10") (pin "2") (pinfunction "2_2") (pintype "passive"))
    )
    (net (code "69") (name "Net-(D9-PadK)") (class "Default")
      (node (ref "D9") (pin "K") (pinfunction "K_K") (pintype "passive"))
      (node (ref "R23") (pin "1") (pinfunction "1_1") (pintype "passive"))
    )
    (net (code "70") (name "Net-(D10-PadK)") (class "Default")
      (node (ref "D10") (pin "K") (pinfunction "K_K") (pintype "passive"))
      (node (ref "R26") (pin "1") (pinfunction "1_1") (pintype "passive"))
    )
    (net (code "71") (name "Net-(ESP1-CH_PD)") (class "Default")
      (node (ref "ESP1") (pin "3") (pinfunction "CH_PD_3") (pintype "passive"))
      (node (ref "R17") (pin "2") (pinfunction "2_2") (pintype "passive"))
    )
    (net (code "72") (name "Net-(ESP1-GPIO0)") (class "Default")
      (node (ref "ESP1") (pin "18") (pinfunction "GPIO0_18") (pintype "passive"))
      (node (ref "P2") (pin "1") (pinfunction "1_1") (pintype "passive"))
    )
    (net (code "73") (name "Net-(ESP1-GPIO15)") (class "Default")
      (node (ref "ESP1") (pin "16") (pinfunction "GPIO15_16") (pintype "passive"))
      (node (ref "R18") (pin "1") (pinfunction "1_1") (pintype "passive"))
    )
    (net (code "74") (name "Net-(R11-Pad2)") (class "Default")
      (node (ref "R11") (pin "2") (pinfunction "2_2") (pintype "passive"))
      (node (ref "R12") (pin "1") (pinfunction "1_1") (pintype "passive"))
    )
    (net (code "75") (name "Net-(U1-BP{slash}FB)") (class "Default")
      (node (ref "C8") (pin "1") (pinfunction "1_1") (pintype "passive"))
      (node (ref "U1") (pin "4") (pinfunction "BP/FB_4") (pintype "passive"))
    )
    (net (code "76") (name "Net-(U1-EN)") (class "Default")
      (node (ref "R7") (pin "2") (pinfunction "2_2") (pintype "passive"))
      (node (ref "U1") (pin "3") (pinfunction "EN_3") (pintype "passive"))
    )
    (net (code "77") (name "Net-(U2-XI)") (class "Default")
      (node (ref "C11") (pin "2") (pinfunction "2_2") (pintype "passive"))
      (node (ref "U2") (pin "7") (pinfunction "XI_7") (pintype "passive"))
      (node (ref "Y1") (pin "1") (pinfunction "OSC1_1") (pintype "passive"))
    )
    (net (code "78") (name "Net-(U2-XO)") (class "Default")
      (node (ref "C12") (pin "2") (pinfunction "2_2") (pintype "passive"))
      (node (ref "U2") (pin "8") (pinfunction "XO_8") (pintype "passive"))
      (node (ref "Y1") (pin "3") (pinfunction "OSC2_3") (pintype "passive"))
    )
    (net (code "79") (name "Net-(U3-PROG)") (class "Default")
      (node (ref "R8") (pin "2") (pinfunction "2_2") (pintype "passive"))
      (node (ref "U3") (pin "2") (pinfunction "PROG_2") (pintype "passive"))
    )
    (net (code "80") (name "Net-(U3-~{CHRG})") (class "Default")
      (node (ref "R9") (pin "1") (pinfunction "1_1") (pintype "passive"))
      (node (ref "U3") (pin "7") (pinfunction "~{CHRG}_7") (pintype "passive"))
    )
    (net (code "81") (name "Net-(U3-~{STDBY})") (class "Default")
      (node (ref "R10") (pin "1") (pinfunction "1_1") (pintype "passive"))
      (node (ref "U3") (pin "6") (pinfunction "~{STDBY}_6") (pintype "passive"))
    )
    (net (code "82") (name "Net-(U6A-PC14-OSC32_IN)") (class "Default")
      (node (ref "R19") (pin "2") (pinfunction "2_2") (pintype "passive"))
      (node (ref "U6") (pin "3") (pinfunction "PC14-OSC32_IN_3") (pintype "bidirectional"))
    )
    (net (code "83") (name "Net-(U6A-PC15-OSC32_OUT)") (class "Default")
      (node (ref "R21") (pin "2") (pinfunction "2_2") (pintype "passive"))
      (node (ref "U6") (pin "4") (pinfunction "PC15-OSC32_OUT_4") (pintype "bidirectional"))
    )
    (net (code "84") (name "Net-(U6A-PD0-OSC_IN)") (class "Default")
      (node (ref "C17") (pin "2") (pinfunction "2_2") (pintype "passive"))
      (node (ref "U6") (pin "5") (pinfunction "PD0-OSC_IN_5") (pintype "bidirectional"))
      (node (ref "Y2") (pin "2") (pinfunction "OSC2_2") (pintype "passive"))
    )
    (net (code "85") (name "Net-(U6A-PD1)") (class "Default")
      (node (ref "C23") (pin "2") (pinfunction "2_2") (pintype "passive"))
      (node (ref "U6") (pin "6") (pinfunction "PD1_6") (pintype "bidirectional"))
      (node (ref "Y2") (pin "1") (pinfunction "OSC1_1") (pintype "passive"))
    )
    (net (code "86") (name "Net-(Y3-OSC1)") (class "Default")
      (node (ref "C30") (pin "2") (pinfunction "2_2") (pintype "passive"))
      (node (ref "R21") (pin "1") (pinfunction "1_1") (pintype "passive"))
      (node (ref "Y3") (pin "1") (pinfunction "OSC1_1") (pintype "passive"))
    )
    (net (code "87") (name "Net-(Y3-OSC2)") (class "Default")
      (node (ref "C24") (pin "2") (pinfunction "2_2") (pintype "passive"))
      (node (ref "R19") (pin "1") (pinfunction "1_1") (pintype "passive"))
      (node (ref "Y3") (pin "2") (pinfunction "OSC2_2") (pintype "passive"))
    )
    (net (code "88") (name "V3") (class "Default")
      (node (ref "C10") (pin "2") (pinfunction "2_2") (pintype "passive"))
      (node (ref "U2") (pin "4") (pinfunction "V3.3_4") (pintype "passive"))
    )
    (net (code "89") (name "VCC") (class "Default")
      (node (ref "C2") (pin "2") (pinfunction "2_2") (pintype "passive"))
      (node (ref "C3") (pin "2") (pinfunction "2_2") (pintype "passive"))
      (node (ref "C4") (pin "2") (pinfunction "2_2") (pintype "passive"))
      (node (ref "D1") (pin "2") (pinfunction "K_2") (pintype "passive"))
      (node (ref "D3") (pin "2") (pinfunction "K_2") (pintype "passive"))
      (node (ref "D4") (pin "A") (pinfunction "A_A") (pintype "passive"))
      (node (ref "R7") (pin "1") (pinfunction "1_1") (pintype "passive"))
      (node (ref "U1") (pin "1") (pinfunction "VIN_1") (pintype "passive"))
    )
    (net (code "90") (name "VFIFT") (class "Default")
      (node (ref "C14") (pin "2") (pinfunction "2_2") (pintype "passive"))
      (node (ref "D7") (pin "A") (pinfunction "A_A") (pintype "passive"))
      (node (ref "D8") (pin "A") (pinfunction "A_A") (pintype "passive"))
      (node (ref "R12") (pin "2") (pinfunction "2_2") (pintype "passive"))
      (node (ref "U3") (pin "4") (pinfunction "VCC_4") (pintype "passive"))
      (node (ref "U3") (pin "8") (pinfunction "CE_8") (pintype "passive"))
    )
    (net (code "91") (name "Vbus") (class "Default")
      (node (ref "C9") (pin "2") (pinfunction "2_2") (pintype "passive"))
      (node (ref "D1") (pin "1") (pinfunction "A_1") (pintype "passive"))
      (node (ref "R11") (pin "1") (pinfunction "1_1") (pintype "passive"))
      (node (ref "R3") (pin "2") (pinfunction "2_2") (pintype "passive"))
      (node (ref "R4") (pin "1") (pinfunction "1_1") (pintype "passive"))
      (node (ref "U2") (pin "16") (pinfunction "VCC_16") (pintype "passive"))
      (node (ref "USB1") (pin "1") (pinfunction "VBUS_1") (pintype "passive"))
    )
    (net (code "92") (name "unconnected-(ESP1-ADC-Pad2)") (class "Default")
      (node (ref "ESP1") (pin "2") (pinfunction "ADC_2") (pintype "passive"))
    )
    (net (code "93") (name "unconnected-(ESP1-GPIO02-Pad17)") (class "Default")
      (node (ref "ESP1") (pin "17") (pinfunction "GPIO02_17") (pintype "passive"))
    )
    (net (code "94") (name "unconnected-(ESP1-GPIO04-Pad19)") (class "Default")
      (node (ref "ESP1") (pin "19") (pinfunction "GPIO04_19") (pintype "passive"))
    )
    (net (code "95") (name "unconnected-(ESP1-GPIO05-Pad20)") (class "Default")
      (node (ref "ESP1") (pin "20") (pinfunction "GPIO05_20") (pintype "passive"))
    )
    (net (code "96") (name "unconnected-(ESP1-GPIO9-Pad11)") (class "Default")
      (node (ref "ESP1") (pin "11") (pinfunction "GPIO9_11") (pintype "passive"))
    )
    (net (code "97") (name "unconnected-(ESP1-GPIO10-Pad12)") (class "Default")
      (node (ref "ESP1") (pin "12") (pinfunction "GPIO10_12") (pintype "passive"))
    )
    (net (code "98") (name "unconnected-(ESP1-GPIO12-Pad6)") (class "Default")
      (node (ref "ESP1") (pin "6") (pinfunction "GPIO12_6") (pintype "passive"))
    )
    (net (code "99") (name "unconnected-(ESP1-GPIO13-Pad7)") (class "Default")
      (node (ref "ESP1") (pin "7") (pinfunction "GPIO13_7") (pintype "passive"))
    )
    (net (code "100") (name "unconnected-(ESP1-GPIO14-Pad5)") (class "Default")
      (node (ref "ESP1") (pin "5") (pinfunction "GPIO14_5") (pintype "passive"))
    )
    (net (code "101") (name "unconnected-(ESP1-GPIO16-Pad4)") (class "Default")
      (node (ref "ESP1") (pin "4") (pinfunction "GPIO16_4") (pintype "passive"))
    )
    (net (code "102") (name "unconnected-(U2-CTS#-Pad9)") (class "Default")
      (node (ref "U2") (pin "9") (pinfunction "CTS#_9") (pintype "passive+no_connect"))
    )
    (net (code "103") (name "unconnected-(U2-DCD#-Pad12)") (class "Default")
      (node (ref "U2") (pin "12") (pinfunction "DCD#_12") (pintype "passive+no_connect"))
    )
    (net (code "104") (name "unconnected-(U2-DSR#-Pad10)") (class "Default")
      (node (ref "U2") (pin "10") (pinfunction "DSR#_10") (pintype "passive+no_connect"))
    )
    (net (code "105") (name "unconnected-(U2-DTR#-Pad13)") (class "Default")
      (node (ref "U2") (pin "13") (pinfunction "DTR#_13") (pintype "passive+no_connect"))
    )
    (net (code "106") (name "unconnected-(U2-R232-Pad15)") (class "Default")
      (node (ref "U2") (pin "15") (pinfunction "R232_15") (pintype "passive+no_connect"))
    )
    (net (code "107") (name "unconnected-(U2-RI#-Pad11)") (class "Default")
      (node (ref "U2") (pin "11") (pinfunction "RI#_11") (pintype "passive+no_connect"))
    )
    (net (code "108") (name "unconnected-(U2-RTS#-Pad14)") (class "Default")
      (node (ref "U2") (pin "14") (pinfunction "RTS#_14") (pintype "passive+no_connect"))
    )
    (net (code "109") (name "unconnected-(U4-NC-Pad9)") (class "Default")
      (node (ref "U4") (pin "9") (pinfunction "NC_9") (pintype "passive"))
    )
    (net (code "110") (name "unconnected-(U6A-PA0-WKUP-Pad14)") (class "Default")
      (node (ref "U6") (pin "14") (pinfunction "PA0-WKUP_14") (pintype "bidirectional"))
    )
    (net (code "111") (name "unconnected-(U6A-PA8-Pad41)") (class "Default")
      (node (ref "U6") (pin "41") (pinfunction "PA8_41") (pintype "bidirectional"))
    )
    (net (code "112") (name "unconnected-(U6A-PB8-Pad61)") (class "Default")
      (node (ref "U6") (pin "61") (pinfunction "PB8_61") (pintype "bidirectional"))
    )
    (net (code "113") (name "unconnected-(U6A-PB9-Pad62)") (class "Default")
      (node (ref "U6") (pin "62") (pinfunction "PB9_62") (pintype "bidirectional"))
    )
    (net (code "114") (name "unconnected-(U6A-PC2-Pad10)") (class "Default")
      (node (ref "U6") (pin "10") (pinfunction "PC2_10") (pintype "bidirectional"))
    )
    (net (code "115") (name "unconnected-(U6A-PC3-Pad11)") (class "Default")
      (node (ref "U6") (pin "11") (pinfunction "PC3_11") (pintype "bidirectional"))
    )
    (net (code "116") (name "unconnected-(U6A-PC13-TAMPER-RTC-Pad2)") (class "Default")
      (node (ref "U6") (pin "2") (pinfunction "PC13-TAMPER-RTC_2") (pintype "bidirectional"))
    )
    (net (code "117") (name "unconnected-(USB1-ID-Pad4)") (class "Default")
      (node (ref "USB1") (pin "4") (pinfunction "ID_4") (pintype "passive+no_connect"))
    )
    (net (code "118") (name "unconnected-(USB1-Shield-Pad0)") (class "Default")
      (node (ref "USB1") (pin "0") (pinfunction "Shield_0") (pintype "passive"))
    )
  )
)
